# SoundDetectorModule.net
KiCad netlist of a schematic drawn in EAGLE
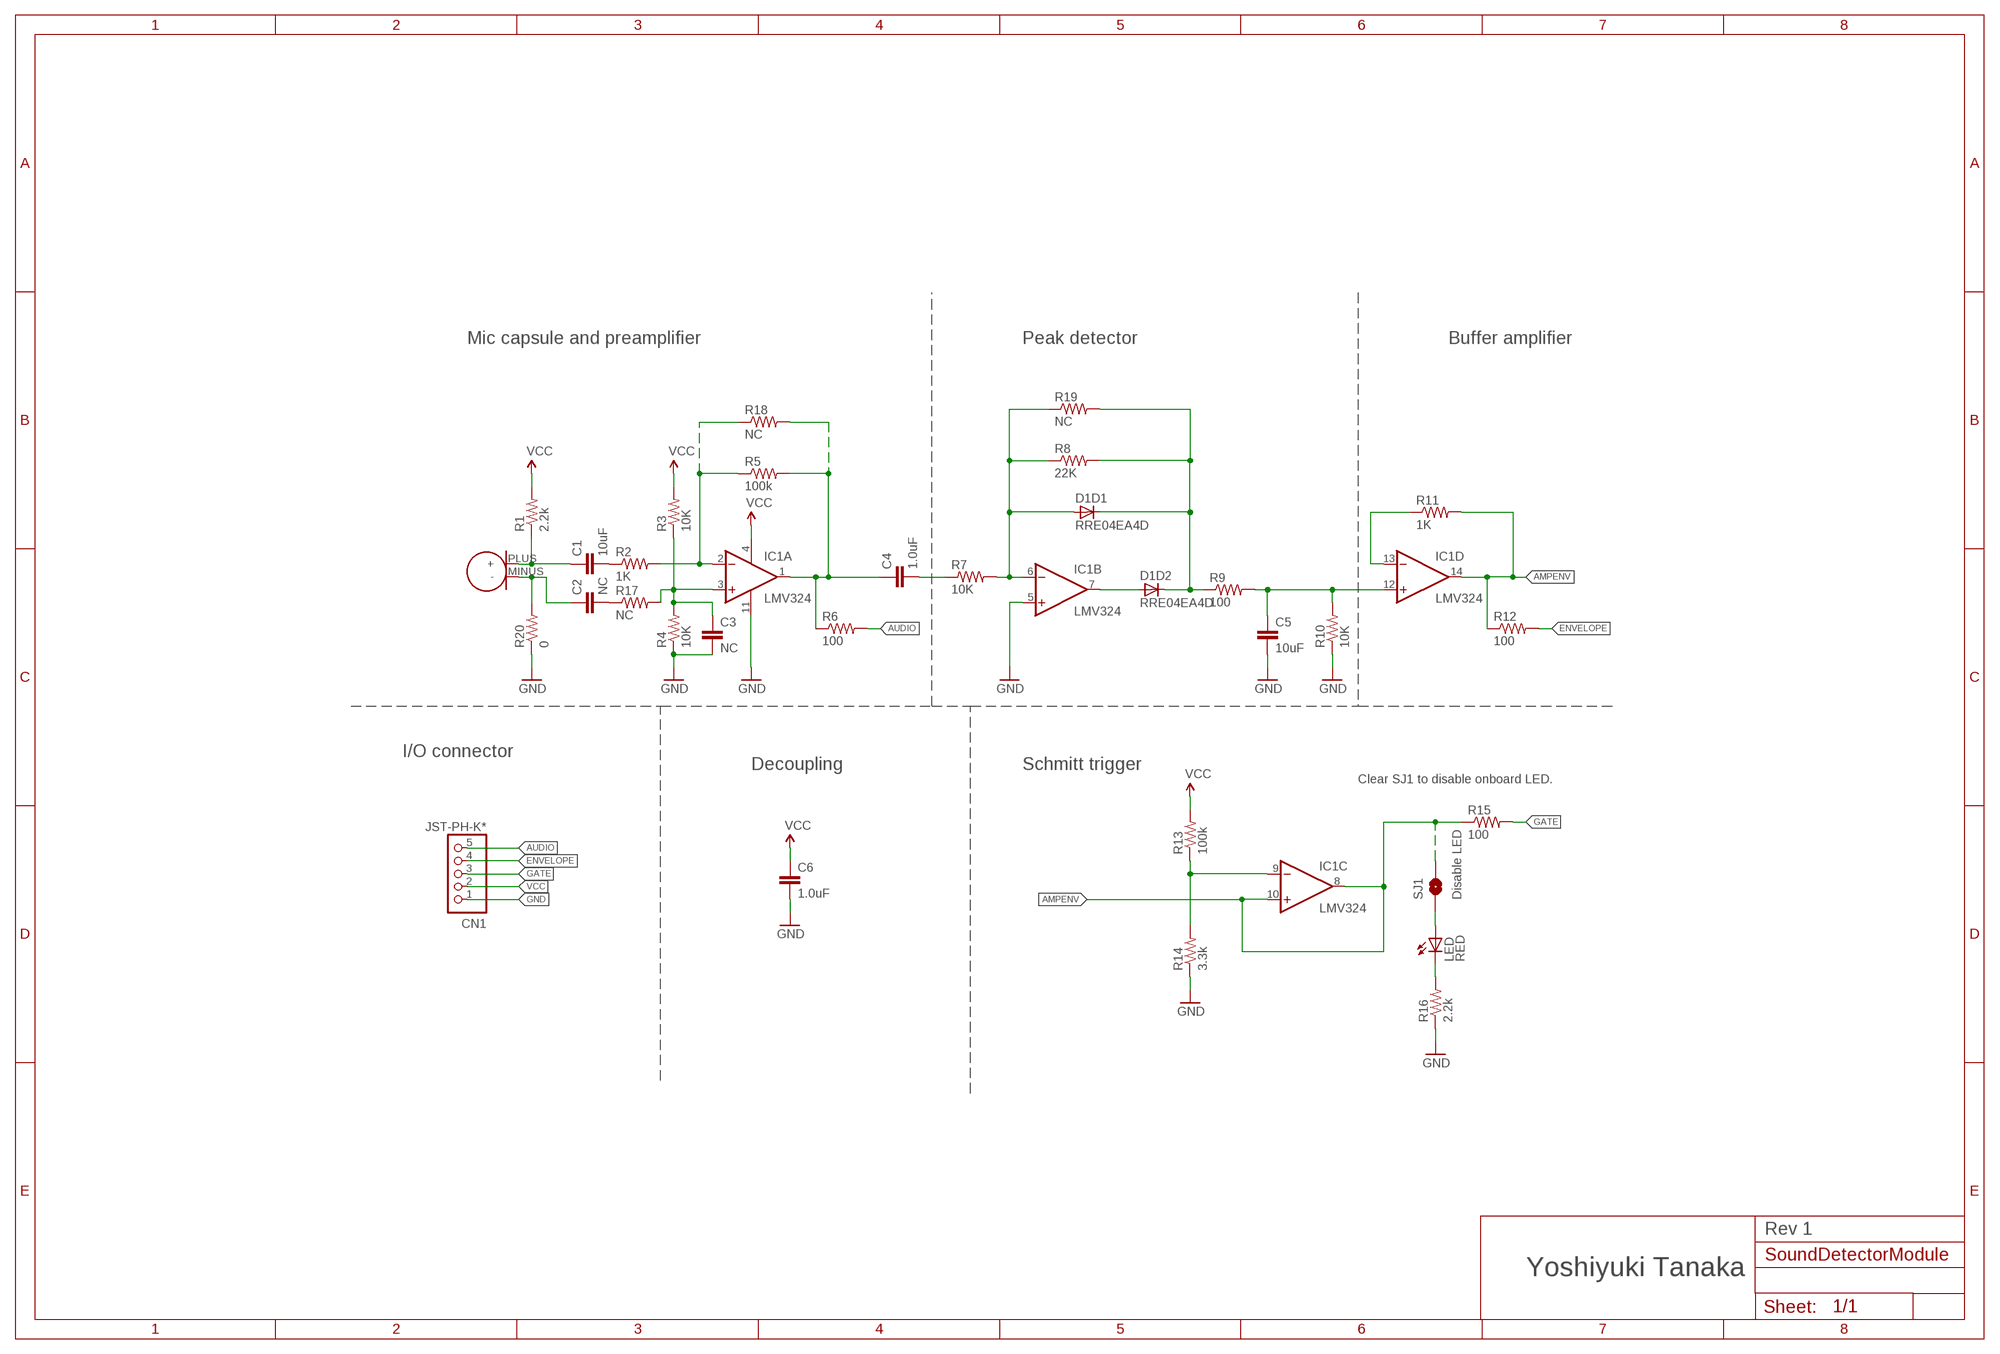
[diagram p0: schematic, sheet 1]

(export (version "E")
  (design (tool "Eeschema 10.0.6"))
  (components
    (comp (ref "A1")
      (value "MO093803-3")
      (footprint "eagle-import:MO093803-3")
      (libsource (lib "eagle-import") (part "MO093803-3"))
    )
    (comp (ref "C1")
      (value "10uF")
      (footprint "eagle-import:C1206")
      (libsource (lib "eagle-import") (part "C-EUC1206"))
    )
    (comp (ref "C2")
      (value "NC")
      (footprint "eagle-import:C0603")
      (libsource (lib "eagle-import") (part "C-EUC0603"))
    )
    (comp (ref "C3")
      (value "NC")
      (footprint "eagle-import:C0603")
      (libsource (lib "eagle-import") (part "C-EUC0603"))
    )
    (comp (ref "C4")
      (value "1.0uF")
      (footprint "eagle-import:C0603")
      (libsource (lib "eagle-import") (part "C-EUC0603"))
    )
    (comp (ref "C5")
      (value "10uF")
      (footprint "eagle-import:C1206")
      (libsource (lib "eagle-import") (part "C-EUC1206"))
    )
    (comp (ref "C6")
      (value "1.0uF")
      (footprint "eagle-import:C0603")
      (libsource (lib "eagle-import") (part "C-EUC0603"))
    )
    (comp (ref "CN1")
      (value "JST-PH-K*")
      (footprint "eagle-import:B5B-PH-SM4-TB")
      (libsource (lib "eagle-import") (part "B5B-PH-SM4-TB"))
    )
    (comp (ref "D1")
      (value "RRE04EA4D")
      (footprint "eagle-import:TSMD5")
      (libsource (lib "eagle-import") (part "RRE04EA4D"))
    )
    (comp (ref "IC1")
      (value "LMV324")
      (footprint "eagle-import:SO14")
      (libsource (lib "eagle-import") (part "LMV324"))
    )
    (comp (ref "LED")
      (value "RED")
      (footprint "eagle-import:SML-E1X")
      (libsource (lib "eagle-import") (part "SML-E1X"))
    )
    (comp (ref "R1")
      (value "2.2k")
      (footprint "eagle-import:R0603")
      (libsource (lib "eagle-import") (part "R-US_R0603"))
    )
    (comp (ref "R2")
      (value "1K")
      (footprint "eagle-import:R0603")
      (libsource (lib "eagle-import") (part "R-US_R0603"))
    )
    (comp (ref "R3")
      (value "10K")
      (footprint "eagle-import:R0603")
      (libsource (lib "eagle-import") (part "R-US_R0603"))
    )
    (comp (ref "R4")
      (value "10K")
      (footprint "eagle-import:R0603")
      (libsource (lib "eagle-import") (part "R-US_R0603"))
    )
    (comp (ref "R5")
      (value "100k")
      (footprint "eagle-import:R0603")
      (libsource (lib "eagle-import") (part "R-US_R0603"))
    )
    (comp (ref "R6")
      (value "100")
      (footprint "eagle-import:R0603")
      (libsource (lib "eagle-import") (part "R-US_R0603"))
    )
    (comp (ref "R7")
      (value "10K")
      (footprint "eagle-import:R0603")
      (libsource (lib "eagle-import") (part "R-US_R0603"))
    )
    (comp (ref "R8")
      (value "22K")
      (footprint "eagle-import:R0603")
      (libsource (lib "eagle-import") (part "R-US_R0603"))
    )
    (comp (ref "R9")
      (value "100")
      (footprint "eagle-import:R0603")
      (libsource (lib "eagle-import") (part "R-US_R0603"))
    )
    (comp (ref "R10")
      (value "10K")
      (footprint "eagle-import:R0603")
      (libsource (lib "eagle-import") (part "R-US_R0603"))
    )
    (comp (ref "R11")
      (value "1K")
      (footprint "eagle-import:R0603")
      (libsource (lib "eagle-import") (part "R-US_R0603"))
    )
    (comp (ref "R12")
      (value "100")
      (footprint "eagle-import:R0603")
      (libsource (lib "eagle-import") (part "R-US_R0603"))
    )
    (comp (ref "R13")
      (value "100k")
      (footprint "eagle-import:R0603")
      (libsource (lib "eagle-import") (part "R-US_R0603"))
    )
    (comp (ref "R14")
      (value "3.3k")
      (footprint "eagle-import:R0603")
      (libsource (lib "eagle-import") (part "R-US_R0603"))
    )
    (comp (ref "R15")
      (value "100")
      (footprint "eagle-import:R0603")
      (libsource (lib "eagle-import") (part "R-US_R0603"))
    )
    (comp (ref "R16")
      (value "2.2k")
      (footprint "eagle-import:R0603")
      (libsource (lib "eagle-import") (part "R-US_R0603"))
    )
    (comp (ref "R17")
      (value "NC")
      (footprint "eagle-import:R0603")
      (libsource (lib "eagle-import") (part "R-US_R0603"))
    )
    (comp (ref "R18")
      (value "NC")
      (footprint "eagle-import:0207_7")
      (libsource (lib "eagle-import") (part "resistor_R-US_0207/7"))
    )
    (comp (ref "R19")
      (value "NC")
      (footprint "eagle-import:0207_7")
      (libsource (lib "eagle-import") (part "resistor_R-US_0207/7"))
    )
    (comp (ref "R20")
      (value "0")
      (footprint "eagle-import:R0603")
      (libsource (lib "eagle-import") (part "R-US_R0603"))
    )
    (comp (ref "SJ1")
      (value "Disable LED")
      (footprint "eagle-import:SJ_2S")
      (libsource (lib "eagle-import") (part "SOLDERJUMPERNC"))
    )
  )
  (nets
    (net (code "1") (name "AMPENV") (class "Default")
      (node (ref "IC1") (pin "10") (pinfunction "+IN_10") (pintype "input"))
      (node (ref "IC1") (pin "14") (pinfunction "OUT_14") (pintype "output"))
      (node (ref "IC1") (pin "8") (pinfunction "OUT_8") (pintype "output"))
      (node (ref "R11") (pin "2") (pinfunction "2_2") (pintype "passive"))
      (node (ref "R12") (pin "1") (pinfunction "1_1") (pintype "passive"))
      (node (ref "R15") (pin "1") (pinfunction "1_1") (pintype "passive"))
      (node (ref "SJ1") (pin "2") (pinfunction "2_2") (pintype "passive"))
    )
    (net (code "2") (name "AUDIO") (class "Default")
      (node (ref "CN1") (pin "5") (pinfunction "5_5") (pintype "passive"))
      (node (ref "R6") (pin "2") (pinfunction "2_2") (pintype "passive"))
    )
    (net (code "3") (name "ENVELOPE") (class "Default")
      (node (ref "CN1") (pin "4") (pinfunction "4_4") (pintype "passive"))
      (node (ref "R12") (pin "2") (pinfunction "2_2") (pintype "passive"))
    )
    (net (code "4") (name "GATE") (class "Default")
      (node (ref "CN1") (pin "3") (pinfunction "3_3") (pintype "passive"))
      (node (ref "R15") (pin "2") (pinfunction "2_2") (pintype "passive"))
    )
    (net (code "5") (name "GND") (class "Default")
      (node (ref "C3") (pin "2") (pinfunction "2_2") (pintype "passive"))
      (node (ref "C5") (pin "2") (pinfunction "2_2") (pintype "passive"))
      (node (ref "C6") (pin "2") (pinfunction "2_2") (pintype "passive"))
      (node (ref "CN1") (pin "1") (pinfunction "1_1") (pintype "passive"))
      (node (ref "IC1") (pin "11") (pinfunction "V-_11") (pintype "power_in"))
      (node (ref "IC1") (pin "5") (pinfunction "+IN_5") (pintype "input"))
      (node (ref "R10") (pin "1") (pinfunction "1_1") (pintype "passive"))
      (node (ref "R14") (pin "1") (pinfunction "1_1") (pintype "passive"))
      (node (ref "R16") (pin "1") (pinfunction "1_1") (pintype "passive"))
      (node (ref "R20") (pin "1") (pinfunction "1_1") (pintype "passive"))
      (node (ref "R4") (pin "1") (pinfunction "1_1") (pintype "passive"))
    )
    (net (code "6") (name "Net-(A1-+)") (class "Default")
      (node (ref "A1") (pin "PLUS") (pinfunction "+_PLUS") (pintype "bidirectional"))
      (node (ref "C1") (pin "1") (pinfunction "1_1") (pintype "passive"))
      (node (ref "R1") (pin "1") (pinfunction "1_1") (pintype "passive"))
    )
    (net (code "7") (name "Net-(A1--)") (class "Default")
      (node (ref "A1") (pin "MINUS") (pinfunction "-_MINUS") (pintype "bidirectional"))
      (node (ref "C2") (pin "1") (pinfunction "1_1") (pintype "passive"))
      (node (ref "R20") (pin "2") (pinfunction "2_2") (pintype "passive"))
    )
    (net (code "8") (name "Net-(C1-Pad2)") (class "Default")
      (node (ref "C1") (pin "2") (pinfunction "2_2") (pintype "passive"))
      (node (ref "R2") (pin "1") (pinfunction "1_1") (pintype "passive"))
    )
    (net (code "9") (name "Net-(C2-Pad2)") (class "Default")
      (node (ref "C2") (pin "2") (pinfunction "2_2") (pintype "passive"))
      (node (ref "R17") (pin "1") (pinfunction "1_1") (pintype "passive"))
    )
    (net (code "10") (name "Net-(C4-Pad2)") (class "Default")
      (node (ref "C4") (pin "2") (pinfunction "2_2") (pintype "passive"))
      (node (ref "R7") (pin "1") (pinfunction "1_1") (pintype "passive"))
    )
    (net (code "11") (name "Net-(D1A-A)") (class "Default")
      (node (ref "D1") (pin "1") (pinfunction "A_1") (pintype "passive"))
      (node (ref "IC1") (pin "6") (pinfunction "-IN_6") (pintype "input"))
      (node (ref "R19") (pin "1") (pinfunction "1_1") (pintype "passive"))
      (node (ref "R7") (pin "2") (pinfunction "2_2") (pintype "passive"))
      (node (ref "R8") (pin "1") (pinfunction "1_1") (pintype "passive"))
    )
    (net (code "12") (name "Net-(D1A-C)") (class "Default")
      (node (ref "D1") (pin "4") (pinfunction "C_4") (pintype "passive"))
      (node (ref "D1") (pin "5") (pinfunction "C_5") (pintype "passive"))
      (node (ref "R19") (pin "2") (pinfunction "2_2") (pintype "passive"))
      (node (ref "R8") (pin "2") (pinfunction "2_2") (pintype "passive"))
      (node (ref "R9") (pin "1") (pinfunction "1_1") (pintype "passive"))
    )
    (net (code "13") (name "Net-(D1B-A)") (class "Default")
      (node (ref "D1") (pin "3") (pinfunction "A_3") (pintype "passive"))
      (node (ref "IC1") (pin "7") (pinfunction "OUT_7") (pintype "output"))
    )
    (net (code "14") (name "Net-(IC1A-+IN)") (class "Default")
      (node (ref "C3") (pin "1") (pinfunction "1_1") (pintype "passive"))
      (node (ref "IC1") (pin "3") (pinfunction "+IN_3") (pintype "input"))
      (node (ref "R17") (pin "2") (pinfunction "2_2") (pintype "passive"))
      (node (ref "R3") (pin "1") (pinfunction "1_1") (pintype "passive"))
      (node (ref "R4") (pin "2") (pinfunction "2_2") (pintype "passive"))
    )
    (net (code "15") (name "Net-(IC1A--IN)") (class "Default")
      (node (ref "IC1") (pin "2") (pinfunction "-IN_2") (pintype "input"))
      (node (ref "R18") (pin "1") (pinfunction "1_1") (pintype "passive"))
      (node (ref "R2") (pin "2") (pinfunction "2_2") (pintype "passive"))
      (node (ref "R5") (pin "1") (pinfunction "1_1") (pintype "passive"))
    )
    (net (code "16") (name "Net-(IC1A-OUT)") (class "Default")
      (node (ref "C4") (pin "1") (pinfunction "1_1") (pintype "passive"))
      (node (ref "IC1") (pin "1") (pinfunction "OUT_1") (pintype "output"))
      (node (ref "R18") (pin "2") (pinfunction "2_2") (pintype "passive"))
      (node (ref "R5") (pin "2") (pinfunction "2_2") (pintype "passive"))
      (node (ref "R6") (pin "1") (pinfunction "1_1") (pintype "passive"))
    )
    (net (code "17") (name "Net-(IC1C--IN)") (class "Default")
      (node (ref "IC1") (pin "9") (pinfunction "-IN_9") (pintype "input"))
      (node (ref "R13") (pin "1") (pinfunction "1_1") (pintype "passive"))
      (node (ref "R14") (pin "2") (pinfunction "2_2") (pintype "passive"))
    )
    (net (code "18") (name "Net-(IC1D-+IN)") (class "Default")
      (node (ref "C5") (pin "1") (pinfunction "1_1") (pintype "passive"))
      (node (ref "IC1") (pin "12") (pinfunction "+IN_12") (pintype "input"))
      (node (ref "R10") (pin "2") (pinfunction "2_2") (pintype "passive"))
      (node (ref "R9") (pin "2") (pinfunction "2_2") (pintype "passive"))
    )
    (net (code "19") (name "Net-(IC1D--IN)") (class "Default")
      (node (ref "IC1") (pin "13") (pinfunction "-IN_13") (pintype "input"))
      (node (ref "R11") (pin "1") (pinfunction "1_1") (pintype "passive"))
    )
    (net (code "20") (name "Net-(LED-PadA)") (class "Default")
      (node (ref "LED") (pin "A") (pinfunction "A_A") (pintype "passive"))
      (node (ref "SJ1") (pin "1") (pinfunction "1_1") (pintype "passive"))
    )
    (net (code "21") (name "Net-(LED-PadC)") (class "Default")
      (node (ref "LED") (pin "C") (pinfunction "C_C") (pintype "passive"))
      (node (ref "R16") (pin "2") (pinfunction "2_2") (pintype "passive"))
    )
    (net (code "22") (name "VCC") (class "Default")
      (node (ref "C6") (pin "1") (pinfunction "1_1") (pintype "passive"))
      (node (ref "CN1") (pin "2") (pinfunction "2_2") (pintype "passive"))
      (node (ref "IC1") (pin "4") (pinfunction "V+_4") (pintype "power_in"))
      (node (ref "R1") (pin "2") (pinfunction "2_2") (pintype "passive"))
      (node (ref "R13") (pin "2") (pinfunction "2_2") (pintype "passive"))
      (node (ref "R3") (pin "2") (pinfunction "2_2") (pintype "passive"))
    )
  )
)
